# ControleSSR.net
KiCad netlist of a schematic drawn in Altium Designer
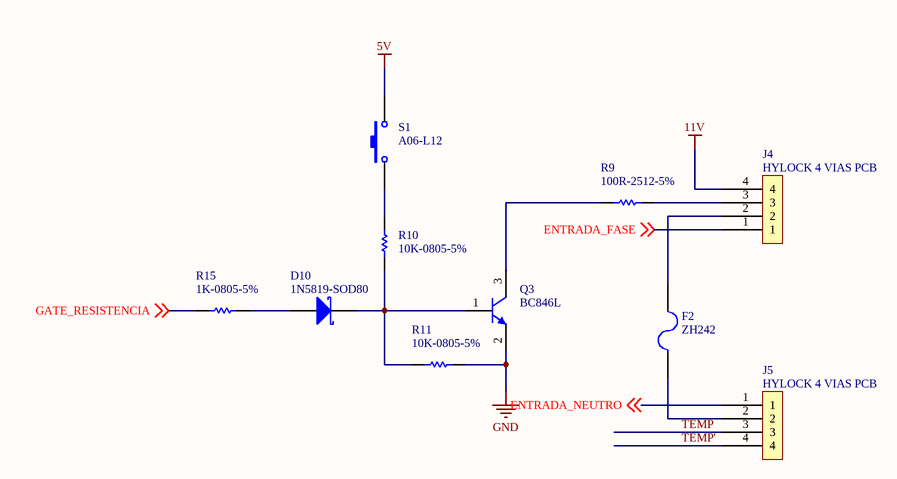
[diagram p0: ControleSSR.SchDoc]

(export (version "E")
  (design (tool "Eeschema 10.0.6"))
  (components
    (comp (ref "D10")
      (value "1N5819-SOD80")
      (footprint "MINIMLEF/SOD80 - REVISADO ONDA")
      (libsource (lib "AquinoLib") (part "1N5819-SOD80"))
    )
    (comp (ref "F2")
      (value "ZH242")
      (footprint "ZH242_REVISADO")
      (description "PORTA FUSÍVEL TIPO BERÇO")
      (libsource (lib "ChaveDigital3") (part "PORTA FUSÍVEL TIPO BERÇO"))
    )
    (comp (ref "J4")
      (value "HYLOCK 4 VIAS PCB")
      (footprint "CONECTOR HYLOK 4 VIAS")
      (description "PCMC2-4")
      (libsource (lib "AquinoLib") (part "PCMC2-4"))
    )
    (comp (ref "J5")
      (value "HYLOCK 4 VIAS PCB")
      (footprint "CONECTOR HYLOK 4 VIAS")
      (description "PCMC2-4")
      (libsource (lib "") (part "PCMC2-4_1"))
    )
    (comp (ref "Q3") (value "BC846L") (libsource (lib "AquinoLib") (part "BC846")))
    (comp (ref "R9")
      (value "100R-2512-5%")
      (footprint "2512 - REVISADO ONDA")
      (description "100R-0805-5%")
      (libsource (lib "AquinoLib") (part "100R-0805-5%"))
    )
    (comp (ref "R10")
      (value "10K-0805-5%")
      (footprint "0805-REVISADO ONDA")
      (description "1K-0805-5%")
      (libsource (lib "AquinoLib") (part "1K-0805-5%"))
    )
    (comp (ref "R11")
      (value "10K-0805-5%")
      (footprint "0805-REVISADO ONDA")
      (libsource (lib "AquinoLib") (part "10K-0805-5%"))
    )
    (comp (ref "R15")
      (value "1K-0805-5%")
      (footprint "0805-REVISADO ONDA")
      (libsource (lib "AquinoLib") (part "1K-0805-5%"))
    )
    (comp (ref "S1")
      (value "A06-L12")
      (footprint "CHAVE_A06")
      (libsource (lib "ChaveDigital3") (part "A06-L12"))
    )
  )
  (nets
    (net (code "1") (name "/TEMP") (class "Default")
      (node (ref "J5") (pin "3") (pinfunction "3_3") (pintype "passive"))
    )
    (net (code "2") (name "/TEMP'") (class "Default")
      (node (ref "J5") (pin "4") (pinfunction "4_4") (pintype "passive"))
    )
    (net (code "3") (name "5V") (class "Default")
      (node (ref "S1") (pin "2") (pinfunction "2_2") (pintype "passive"))
    )
    (net (code "4") (name "11V") (class "Default")
      (node (ref "J4") (pin "4") (pinfunction "4_4") (pintype "passive"))
    )
    (net (code "5") (name "ENTRADA_FASE") (class "Default")
      (node (ref "J4") (pin "1") (pinfunction "1_1") (pintype "passive"))
    )
    (net (code "6") (name "ENTRADA_NEUTRO") (class "Default")
      (node (ref "J5") (pin "1") (pinfunction "1_1") (pintype "passive"))
    )
    (net (code "7") (name "GATE_RESISTENCIA") (class "Default")
      (node (ref "R15") (pin "1") (pinfunction "1_1") (pintype "passive"))
    )
    (net (code "8") (name "GND") (class "Default")
      (node (ref "Q3") (pin "2") (pinfunction "E_2") (pintype "passive"))
      (node (ref "R11") (pin "2") (pinfunction "2_2") (pintype "passive"))
    )
    (net (code "9") (name "Net-(D10-A)") (class "Default")
      (node (ref "D10") (pin "1") (pinfunction "A_1") (pintype "passive"))
      (node (ref "R15") (pin "2") (pinfunction "2_2") (pintype "passive"))
    )
    (net (code "10") (name "Net-(D10-K)") (class "Default")
      (node (ref "D10") (pin "2") (pinfunction "K_2") (pintype "passive"))
      (node (ref "Q3") (pin "1") (pinfunction "B_1") (pintype "passive"))
      (node (ref "R10") (pin "1") (pinfunction "1_1") (pintype "passive"))
      (node (ref "R11") (pin "1") (pinfunction "1_1") (pintype "passive"))
    )
    (net (code "11") (name "Net-(F2-Pad1)") (class "Default")
      (node (ref "F2") (pin "1") (pinfunction "1_1") (pintype "passive"))
      (node (ref "J4") (pin "2") (pinfunction "2_2") (pintype "passive"))
    )
    (net (code "12") (name "Net-(F2-Pad2)") (class "Default")
      (node (ref "F2") (pin "2") (pinfunction "2_2") (pintype "passive"))
      (node (ref "J5") (pin "2") (pinfunction "2_2") (pintype "passive"))
    )
    (net (code "13") (name "Net-(J4-Pad3)") (class "Default")
      (node (ref "J4") (pin "3") (pinfunction "3_3") (pintype "passive"))
      (node (ref "R9") (pin "2") (pinfunction "2_2") (pintype "passive"))
    )
    (net (code "14") (name "Net-(Q3-C)") (class "Default")
      (node (ref "Q3") (pin "3") (pinfunction "C_3") (pintype "passive"))
      (node (ref "R9") (pin "1") (pinfunction "1_1") (pintype "passive"))
    )
    (net (code "15") (name "Net-(R10-Pad2)") (class "Default")
      (node (ref "R10") (pin "2") (pinfunction "2_2") (pintype "passive"))
      (node (ref "S1") (pin "1") (pinfunction "1_1") (pintype "passive"))
    )
  )
)
